# Rocketometer2148_MPU6000.net
KiCad netlist of a schematic drawn in EAGLE
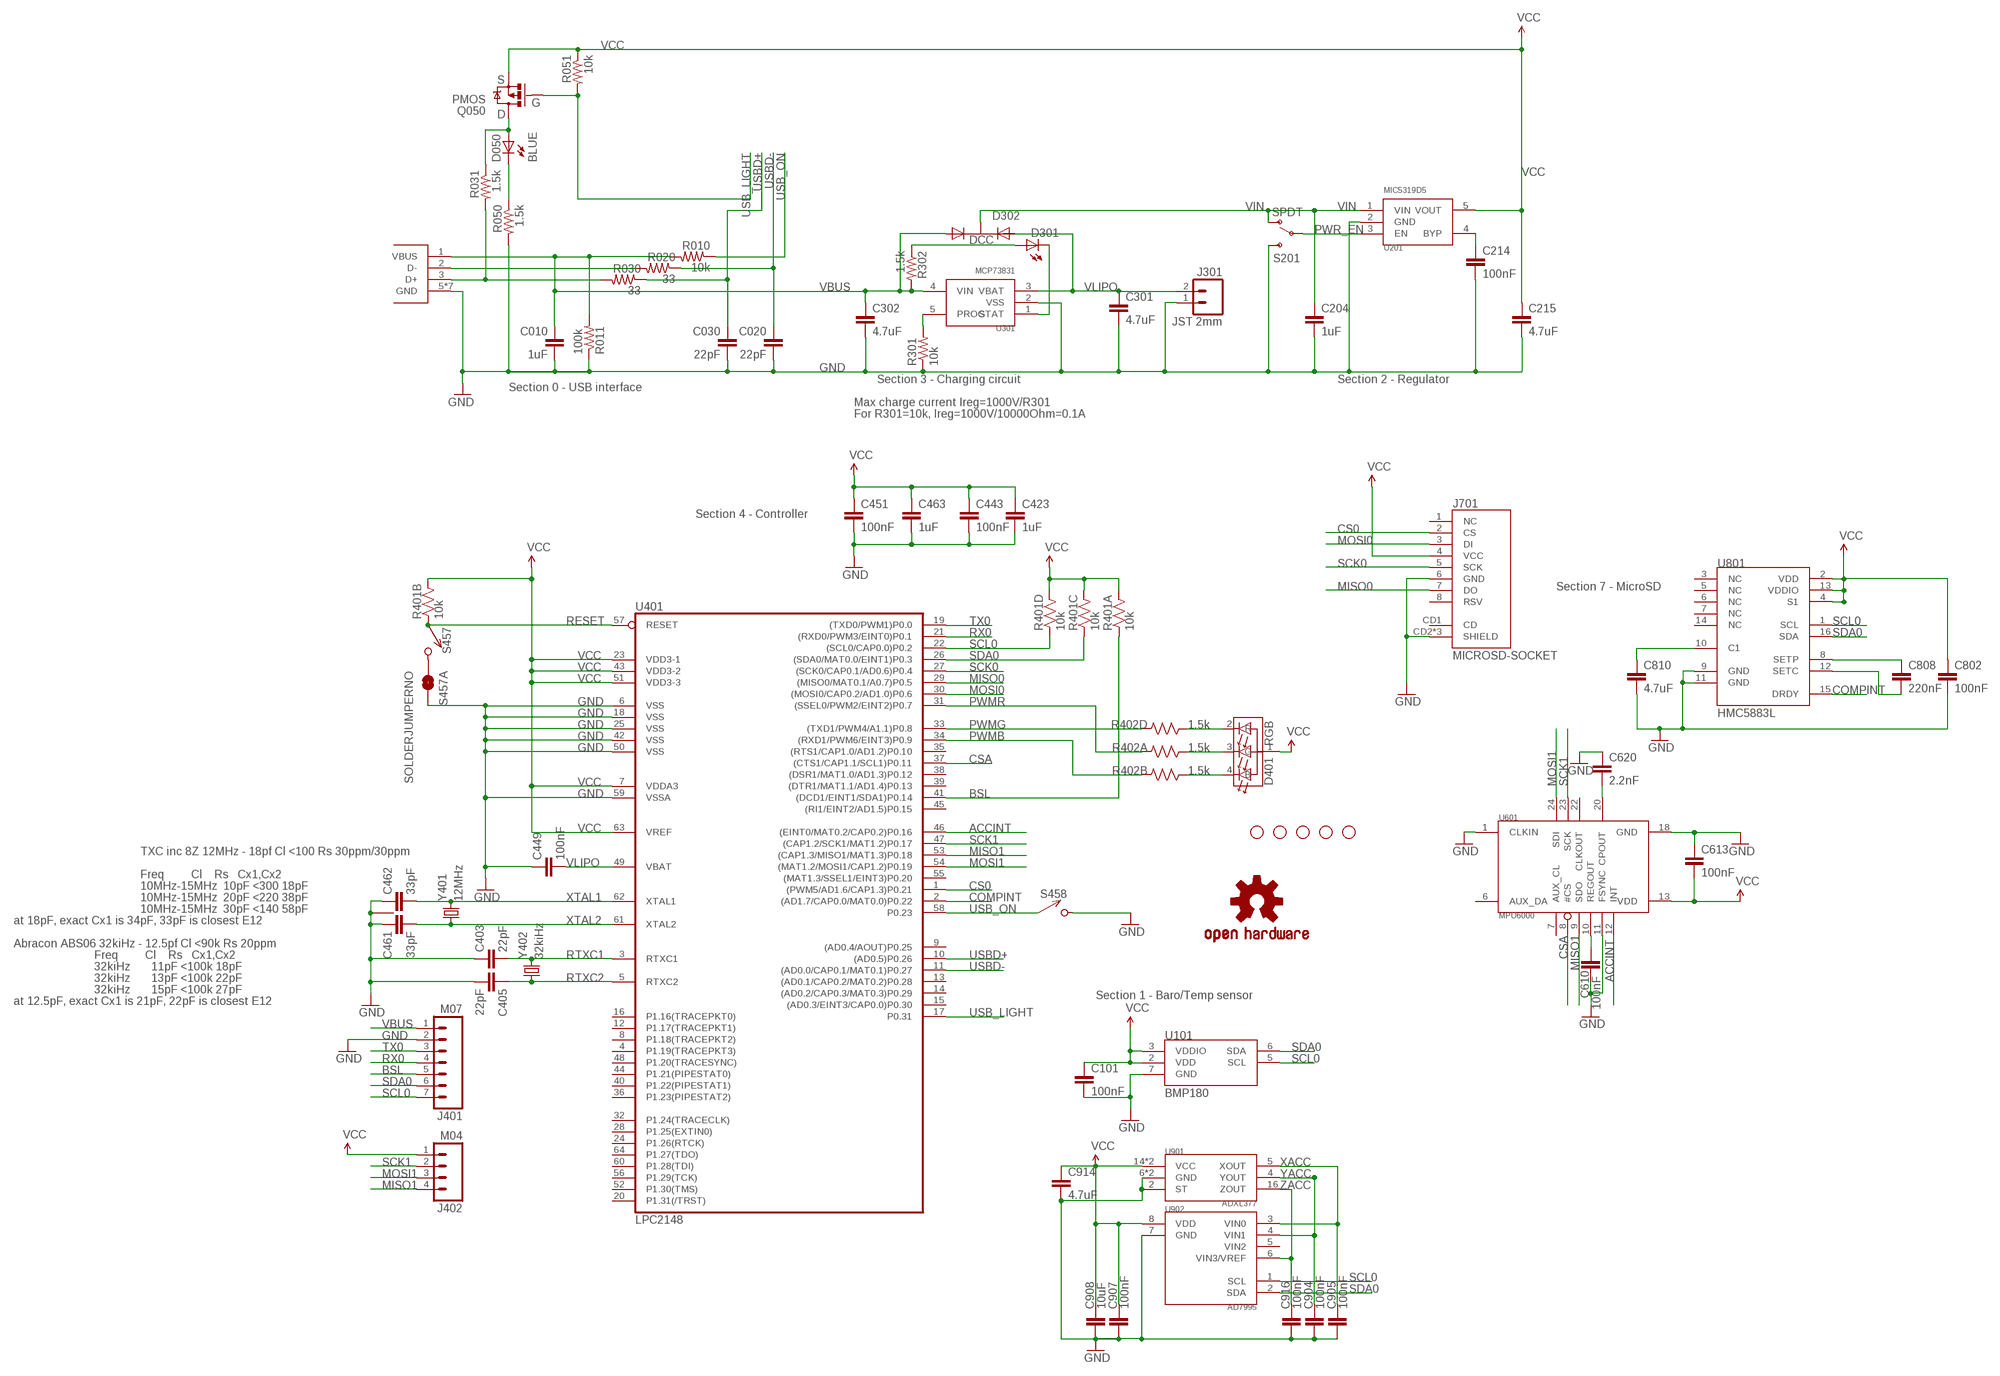
[diagram p0: schematic, sheet 1]

(export (version "E")
  (design (tool "Eeschema 10.0.6"))
  (components
    (comp (ref "C010")
      (value "1uF")
      (footprint "eagle-import:0402-CAP")
      (libsource (lib "eagle-import") (part "CAP0402-CAP"))
    )
    (comp (ref "C020")
      (value "22pF")
      (footprint "eagle-import:0402-CAP")
      (libsource (lib "eagle-import") (part "CAP0402-CAP"))
    )
    (comp (ref "C030")
      (value "22pF")
      (footprint "eagle-import:0402-CAP")
      (libsource (lib "eagle-import") (part "CAP0402-CAP"))
    )
    (comp (ref "C101")
      (value "100nF")
      (footprint "eagle-import:0402-CAP")
      (libsource (lib "eagle-import") (part "CAP0402-CAP"))
    )
    (comp (ref "C204")
      (value "1uF")
      (footprint "eagle-import:0402-CAP")
      (libsource (lib "eagle-import") (part "CAP0402-CAP"))
    )
    (comp (ref "C214")
      (value "100nF")
      (footprint "eagle-import:0402-CAP")
      (libsource (lib "eagle-import") (part "CAP0402-CAP"))
    )
    (comp (ref "C215")
      (value "4.7uF")
      (footprint "eagle-import:0402-CAP")
      (libsource (lib "eagle-import") (part "CAP0402-CAP"))
    )
    (comp (ref "C301")
      (value "4.7uF")
      (footprint "eagle-import:0402-CAP")
      (libsource (lib "eagle-import") (part "CAP0402-CAP"))
    )
    (comp (ref "C302")
      (value "4.7uF")
      (footprint "eagle-import:0402-CAP")
      (libsource (lib "eagle-import") (part "CAP0402-CAP"))
    )
    (comp (ref "C403")
      (value "22pF")
      (footprint "eagle-import:0402-CAP")
      (libsource (lib "eagle-import") (part "CAP0402-CAP"))
    )
    (comp (ref "C405")
      (value "22pF")
      (footprint "eagle-import:0402-CAP")
      (libsource (lib "eagle-import") (part "CAP0402-CAP"))
    )
    (comp (ref "C423")
      (value "1uF")
      (footprint "eagle-import:0402-CAP")
      (libsource (lib "eagle-import") (part "CAP0402-CAP"))
    )
    (comp (ref "C443")
      (value "100nF")
      (footprint "eagle-import:0402-CAP")
      (libsource (lib "eagle-import") (part "CAP0402-CAP"))
    )
    (comp (ref "C449")
      (value "100nF")
      (footprint "eagle-import:0402-CAP")
      (libsource (lib "eagle-import") (part "CAP0402-CAP"))
    )
    (comp (ref "C451")
      (value "100nF")
      (footprint "eagle-import:0402-CAP")
      (libsource (lib "eagle-import") (part "CAP0402-CAP"))
    )
    (comp (ref "C461")
      (value "33pF")
      (footprint "eagle-import:0402-CAP")
      (libsource (lib "eagle-import") (part "CAP0402-CAP"))
    )
    (comp (ref "C462")
      (value "33pF")
      (footprint "eagle-import:0402-CAP")
      (libsource (lib "eagle-import") (part "CAP0402-CAP"))
    )
    (comp (ref "C463")
      (value "1uF")
      (footprint "eagle-import:0402-CAP")
      (libsource (lib "eagle-import") (part "CAP0402-CAP"))
    )
    (comp (ref "C610")
      (value "100nF")
      (footprint "eagle-import:0402-CAP")
      (libsource (lib "eagle-import") (part "CAP0402-CAP"))
    )
    (comp (ref "C613")
      (value "100nF")
      (footprint "eagle-import:0402-CAP")
      (libsource (lib "eagle-import") (part "CAP0402-CAP"))
    )
    (comp (ref "C620")
      (value "2.2nF")
      (footprint "eagle-import:0402-CAP")
      (libsource (lib "eagle-import") (part "CAP0402-CAP"))
    )
    (comp (ref "C802")
      (value "100nF")
      (footprint "eagle-import:0402-CAP")
      (libsource (lib "eagle-import") (part "CAP0402-CAP"))
    )
    (comp (ref "C808")
      (value "220nF")
      (footprint "eagle-import:0402-CAP")
      (libsource (lib "eagle-import") (part "CAP0402-CAP"))
    )
    (comp (ref "C810")
      (value "4.7uF")
      (footprint "eagle-import:0402-CAP")
      (libsource (lib "eagle-import") (part "CAP0402-CAP"))
    )
    (comp (ref "C904")
      (value "100nF")
      (footprint "eagle-import:0402-CAP")
      (libsource (lib "eagle-import") (part "CAP0402-CAP"))
    )
    (comp (ref "C905")
      (value "100nF")
      (footprint "eagle-import:0402-CAP")
      (libsource (lib "eagle-import") (part "CAP0402-CAP"))
    )
    (comp (ref "C907")
      (value "100nF")
      (footprint "eagle-import:0402-CAP")
      (libsource (lib "eagle-import") (part "SparkFun-Passives_CAP0402-CAP"))
    )
    (comp (ref "C908")
      (value "10uF")
      (footprint "eagle-import:0603-CAP")
      (libsource (lib "eagle-import") (part "CAP0603-CAP"))
    )
    (comp (ref "C914")
      (value "4.7uF")
      (footprint "eagle-import:0402-CAP")
      (libsource (lib "eagle-import") (part "CAP0402-CAP"))
    )
    (comp (ref "C916")
      (value "100nF")
      (footprint "eagle-import:0402-CAP")
      (libsource (lib "eagle-import") (part "CAP0402-CAP"))
    )
    (comp (ref "D050")
      (value "BLUE")
      (footprint "eagle-import:LED-0603")
      (libsource (lib "eagle-import") (part "LED0603"))
    )
    (comp (ref "D301")
      (value "YELLOW")
      (footprint "eagle-import:LED-0603")
      (libsource (lib "eagle-import") (part "LED0603"))
    )
    (comp (ref "D302")
      (value "DCC")
      (footprint "eagle-import:SOT-23-3")
      (libsource (lib "eagle-import") (part "PMEG2005CT"))
    )
    (comp (ref "D401")
      (value "RGB")
      (footprint "eagle-import:HSMF-C118")
      (libsource (lib "eagle-import") (part "HSMF-C118"))
    )
    (comp (ref "J001")
      (value "USB_MICROB_JST")
      (footprint "eagle-import:UB-MC5BR3-SD204-4S")
      (libsource (lib "eagle-import") (part "USB_MICROB_JST"))
    )
    (comp (ref "J301")
      (value "JST 2mm")
      (footprint "eagle-import:JST-2-SMD")
      (libsource (lib "eagle-import") (part "M02-JST-2MM-SMT"))
    )
    (comp (ref "J401")
      (value "M07")
      (footprint "eagle-import:1X07")
      (libsource (lib "eagle-import") (part "M07"))
    )
    (comp (ref "J402")
      (value "M04")
      (footprint "eagle-import:1X04")
      (libsource (lib "eagle-import") (part "M04PTH"))
    )
    (comp (ref "J701")
      (value "MICROSD-SOCKET")
      (footprint "eagle-import:MICROSD-SOCKET-PP")
      (libsource (lib "eagle-import") (part "MICROSD-SOCKET"))
    )
    (comp (ref "JP1")
      (value "STAND-OFFTIGHT")
      (footprint "eagle-import:STAND-OFF-TIGHT")
      (libsource (lib "eagle-import") (part "STAND-OFFTIGHT"))
    )
    (comp (ref "JP2")
      (value "STAND-OFFTIGHT")
      (footprint "eagle-import:STAND-OFF-TIGHT")
      (libsource (lib "eagle-import") (part "STAND-OFFTIGHT"))
    )
    (comp (ref "JP3")
      (value "STAND-OFFTIGHT")
      (footprint "eagle-import:STAND-OFF-TIGHT")
      (libsource (lib "eagle-import") (part "STAND-OFFTIGHT"))
    )
    (comp (ref "JP4")
      (value "STAND-OFFTIGHT")
      (footprint "eagle-import:STAND-OFF-TIGHT")
      (libsource (lib "eagle-import") (part "STAND-OFFTIGHT"))
    )
    (comp (ref "JP5")
      (value "STAND-OFFTIGHT")
      (footprint "eagle-import:STAND-OFF-TIGHT")
      (libsource (lib "eagle-import") (part "STAND-OFFTIGHT"))
    )
    (comp (ref "Q050")
      (value "PMOS")
      (footprint "eagle-import:SOT23-3")
      (libsource (lib "eagle-import") (part "MOSFET-PCHANNELSMD"))
    )
    (comp (ref "R010")
      (value "10k")
      (footprint "eagle-import:0402-RES")
      (libsource (lib "eagle-import") (part "RESISTOR0402-RES"))
    )
    (comp (ref "R011")
      (value "100k")
      (footprint "eagle-import:0402-RES")
      (libsource (lib "eagle-import") (part "RESISTOR0402-RES"))
    )
    (comp (ref "R020")
      (value "33")
      (footprint "eagle-import:0402-RES")
      (libsource (lib "eagle-import") (part "RESISTOR0402-RES"))
    )
    (comp (ref "R030")
      (value "33")
      (footprint "eagle-import:0402-RES")
      (libsource (lib "eagle-import") (part "RESISTOR0402-RES"))
    )
    (comp (ref "R031")
      (value "1.5k")
      (footprint "eagle-import:0402-RES")
      (libsource (lib "eagle-import") (part "RESISTOR0402-RES"))
    )
    (comp (ref "R050")
      (value "1.5k")
      (footprint "eagle-import:0402-RES")
      (libsource (lib "eagle-import") (part "RESISTOR0402-RES"))
    )
    (comp (ref "R051")
      (value "10k")
      (footprint "eagle-import:0402-RES")
      (libsource (lib "eagle-import") (part "RESISTOR0402-RES"))
    )
    (comp (ref "R301")
      (value "10k")
      (footprint "eagle-import:0402-RES")
      (libsource (lib "eagle-import") (part "RESISTOR0402-RES"))
    )
    (comp (ref "R302")
      (value "1.5k")
      (footprint "eagle-import:0402-RES")
      (libsource (lib "eagle-import") (part "RESISTOR0402-RES"))
    )
    (comp (ref "R401")
      (value "10k")
      (footprint "eagle-import:CRA04")
      (fields (field (name "DIGIKEY") "CRA4S810KCT-ND"))
      (libsource (lib "eagle-import") (part "RP404"))
    )
    (comp (ref "R402")
      (value "1.5k")
      (footprint "eagle-import:CRA04")
      (fields (field (name "DIGIKEY") "CRA4S81.5KCT-ND"))
      (libsource (lib "eagle-import") (part "RP404"))
    )
    (comp (ref "S201")
      (value "SPDT")
      (footprint "eagle-import:AYZ0202")
      (libsource (lib "eagle-import") (part "SWITCH-SPSTSMD"))
    )
    (comp (ref "S457")
      (value "B3U-1000P")
      (footprint "eagle-import:B3U-1000P")
      (libsource (lib "eagle-import") (part "B3U-1000P"))
    )
    (comp (ref "S457A")
      (value "SOLDERJUMPERNO")
      (footprint "eagle-import:SJ_2S-NO")
      (libsource (lib "eagle-import") (part "SOLDERJUMPERNO"))
    )
    (comp (ref "S458")
      (value "B3U-1000P")
      (footprint "eagle-import:B3U-1000P")
      (libsource (lib "eagle-import") (part "B3U-1000P"))
    )
    (comp (ref "U$2")
      (value "OSHW-LOGOS")
      (footprint "eagle-import:OSHW-LOGO-S")
      (libsource (lib "eagle-import") (part "OSHW-LOGOS"))
    )
    (comp (ref "U101")
      (value "BMP180")
      (footprint "eagle-import:BMP180")
      (libsource (lib "eagle-import") (part "BMP180"))
    )
    (comp (ref "U201")
      (value "MIC5319D5")
      (footprint "eagle-import:SOT-23-5")
      (libsource (lib "eagle-import") (part "MIC5319D5"))
    )
    (comp (ref "U301")
      (value "MCP73831")
      (footprint "eagle-import:SOT-23-5")
      (libsource (lib "eagle-import") (part "MCP73831"))
    )
    (comp (ref "U401")
      (value "LPC2148")
      (footprint "eagle-import:SQFP-S-10X10-64")
      (libsource (lib "eagle-import") (part "LPC213X"))
    )
    (comp (ref "U601")
      (value "MPU6000")
      (footprint "eagle-import:MPU60X0")
      (libsource (lib "eagle-import") (part "MPU6000"))
    )
    (comp (ref "U801")
      (value "HMC5883L")
      (footprint "eagle-import:16LPCC")
      (libsource (lib "eagle-import") (part "HMC5883LSMD"))
    )
    (comp (ref "U901")
      (value "ADXL377")
      (footprint "eagle-import:ADXL377")
      (libsource (lib "eagle-import") (part "ADXL377"))
    )
    (comp (ref "U902")
      (value "AD7995")
      (footprint "eagle-import:SOT-23-8")
      (libsource (lib "eagle-import") (part "AD799X"))
    )
    (comp (ref "Y401")
      (value "12MHz")
      (footprint "eagle-import:CRYSTAL_SMD_2MM_2_5MM")
      (fields (field (name "DIGIKEY") "887-1487-1-ND"))
      (libsource (lib "eagle-import") (part "CX2520"))
    )
    (comp (ref "Y402")
      (value "32kiHz")
      (footprint "eagle-import:ABS06")
      (libsource (lib "eagle-import") (part "ABS06"))
    )
  )
  (nets
    (net (code "1") (name "/ACCINT") (class "Default")
      (node (ref "U401") (pin "46") (pinfunction "(EINT0/MAT0.2/CAP0.2)P0.16_46") (pintype "bidirectional"))
      (node (ref "U601") (pin "12") (pinfunction "INT_12") (pintype "output"))
    )
    (net (code "2") (name "/BSL") (class "Default")
      (node (ref "J401") (pin "5") (pinfunction "5_5") (pintype "passive"))
      (node (ref "R401") (pin "1") (pinfunction "1_1") (pintype "passive"))
      (node (ref "U401") (pin "41") (pinfunction "(DCD1/EINT1/SDA1)P0.14_41") (pintype "bidirectional"))
    )
    (net (code "3") (name "/COMPINT") (class "Default")
      (node (ref "U401") (pin "2") (pinfunction "(AD1.7/CAP0.0/MAT0.0)P0.22_2") (pintype "bidirectional"))
      (node (ref "U801") (pin "15") (pinfunction "DRDY_15") (pintype "bidirectional"))
    )
    (net (code "4") (name "/CS0") (class "Default")
      (node (ref "J701") (pin "2") (pinfunction "CS_2") (pintype "bidirectional"))
      (node (ref "U401") (pin "1") (pinfunction "(PWM5/AD1.6/CAP1.3)P0.21_1") (pintype "bidirectional"))
    )
    (net (code "5") (name "/CSA") (class "Default")
      (node (ref "U401") (pin "37") (pinfunction "(CTS1/CAP1.1/SCL1)P0.11_37") (pintype "bidirectional"))
      (node (ref "U601") (pin "8") (pinfunction "#CS_8") (pintype "bidirectional"))
    )
    (net (code "6") (name "/MISO0") (class "Default")
      (node (ref "J701") (pin "7") (pinfunction "DO_7") (pintype "bidirectional"))
      (node (ref "U401") (pin "29") (pinfunction "(MISO0/MAT0.1/A0.7)P0.5_29") (pintype "bidirectional"))
    )
    (net (code "7") (name "/MISO1") (class "Default")
      (node (ref "J402") (pin "4") (pinfunction "4_4") (pintype "passive"))
      (node (ref "U401") (pin "53") (pinfunction "(CAP1.3/MISO1/MAT1.3)P0.18_53") (pintype "bidirectional"))
      (node (ref "U601") (pin "9") (pinfunction "SDO_9") (pintype "output"))
    )
    (net (code "8") (name "/MOSI0") (class "Default")
      (node (ref "J701") (pin "3") (pinfunction "DI_3") (pintype "bidirectional"))
      (node (ref "U401") (pin "30") (pinfunction "(MOSI0/CAP0.2/AD1.0)P0.6_30") (pintype "bidirectional"))
    )
    (net (code "9") (name "/MOSI1") (class "Default")
      (node (ref "J402") (pin "3") (pinfunction "3_3") (pintype "passive"))
      (node (ref "U401") (pin "54") (pinfunction "(MAT1.2/MOSI1/CAP1.2)P0.19_54") (pintype "bidirectional"))
      (node (ref "U601") (pin "24") (pinfunction "SDI_24") (pintype "bidirectional"))
    )
    (net (code "10") (name "/PWMB") (class "Default")
      (node (ref "R402") (pin "7") (pinfunction "2_7") (pintype "passive"))
      (node (ref "U401") (pin "34") (pinfunction "(RXD1/PWM6/EINT3)P0.9_34") (pintype "bidirectional"))
    )
    (net (code "11") (name "/PWMG") (class "Default")
      (node (ref "R402") (pin "5") (pinfunction "2_5") (pintype "passive"))
      (node (ref "U401") (pin "33") (pinfunction "(TXD1/PWM4/A1.1)P0.8_33") (pintype "bidirectional"))
    )
    (net (code "12") (name "/PWMR") (class "Default")
      (node (ref "R402") (pin "8") (pinfunction "2_8") (pintype "passive"))
      (node (ref "U401") (pin "31") (pinfunction "(SSEL0/PWM2/EINT2)P0.7_31") (pintype "bidirectional"))
    )
    (net (code "13") (name "/PWR_EN") (class "Default")
      (node (ref "S201") (pin "2") (pinfunction "P_2") (pintype "passive"))
      (node (ref "U201") (pin "3") (pinfunction "EN_3") (pintype "bidirectional"))
    )
    (net (code "14") (name "/RESET") (class "Default")
      (node (ref "R401") (pin "2") (pinfunction "1_2") (pintype "passive"))
      (node (ref "S457") (pin "P$1") (pinfunction "1_P$1") (pintype "bidirectional"))
      (node (ref "U401") (pin "57") (pinfunction "RESET_57") (pintype "input"))
    )
    (net (code "15") (name "/RTXC1") (class "Default")
      (node (ref "C403") (pin "2") (pinfunction "2_2") (pintype "passive"))
      (node (ref "U401") (pin "3") (pinfunction "RTXC1_3") (pintype "input"))
      (node (ref "Y402") (pin "2") (pinfunction "2_2") (pintype "passive"))
    )
    (net (code "16") (name "/RTXC2") (class "Default")
      (node (ref "C405") (pin "1") (pinfunction "1_1") (pintype "passive"))
      (node (ref "U401") (pin "5") (pinfunction "RTXC2_5") (pintype "output"))
      (node (ref "Y402") (pin "1") (pinfunction "1_1") (pintype "passive"))
    )
    (net (code "17") (name "/RX0") (class "Default")
      (node (ref "J401") (pin "4") (pinfunction "4_4") (pintype "passive"))
      (node (ref "U401") (pin "21") (pinfunction "(RXD0/PWM3/EINT0)P0.1_21") (pintype "bidirectional"))
    )
    (net (code "18") (name "/SCK0") (class "Default")
      (node (ref "J701") (pin "5") (pinfunction "SCK_5") (pintype "bidirectional"))
      (node (ref "U401") (pin "27") (pinfunction "(SCK0/CAP0.1/AD0.6)P0.4_27") (pintype "bidirectional"))
    )
    (net (code "19") (name "/SCK1") (class "Default")
      (node (ref "J402") (pin "2") (pinfunction "2_2") (pintype "passive"))
      (node (ref "U401") (pin "47") (pinfunction "(CAP1.2/SCK1/MAT1.2)P0.17_47") (pintype "bidirectional"))
      (node (ref "U601") (pin "23") (pinfunction "SCK_23") (pintype "bidirectional"))
    )
    (net (code "20") (name "/SCL0") (class "Default")
      (node (ref "J401") (pin "7") (pinfunction "7_7") (pintype "passive"))
      (node (ref "R401") (pin "4") (pinfunction "1_4") (pintype "passive"))
      (node (ref "U101") (pin "5") (pinfunction "SCL_5") (pintype "input"))
      (node (ref "U401") (pin "22") (pinfunction "(SCL0/CAP0.0)P0.2_22") (pintype "bidirectional"))
      (node (ref "U801") (pin "1") (pinfunction "SCL_1") (pintype "bidirectional"))
      (node (ref "U902") (pin "1") (pinfunction "SCL_1") (pintype "bidirectional"))
    )
    (net (code "21") (name "/SDA0") (class "Default")
      (node (ref "J401") (pin "6") (pinfunction "6_6") (pintype "passive"))
      (node (ref "R401") (pin "3") (pinfunction "1_3") (pintype "passive"))
      (node (ref "U101") (pin "6") (pinfunction "SDA_6") (pintype "bidirectional"))
      (node (ref "U401") (pin "26") (pinfunction "(SDA0/MAT0.0/EINT1)P0.3_26") (pintype "bidirectional"))
      (node (ref "U801") (pin "16") (pinfunction "SDA_16") (pintype "bidirectional"))
      (node (ref "U902") (pin "2") (pinfunction "SDA_2") (pintype "bidirectional"))
    )
    (net (code "22") (name "/TX0") (class "Default")
      (node (ref "J401") (pin "3") (pinfunction "3_3") (pintype "passive"))
      (node (ref "U401") (pin "19") (pinfunction "(TXD0/PWM1)P0.0_19") (pintype "bidirectional"))
    )
    (net (code "23") (name "/USBD+") (class "Default")
      (node (ref "C030") (pin "1") (pinfunction "1_1") (pintype "passive"))
      (node (ref "R030") (pin "1") (pinfunction "1_1") (pintype "passive"))
      (node (ref "U401") (pin "10") (pinfunction "(AD0.5)P0.26_10") (pintype "bidirectional"))
    )
    (net (code "24") (name "/USBD-") (class "Default")
      (node (ref "C020") (pin "1") (pinfunction "1_1") (pintype "passive"))
      (node (ref "R020") (pin "1") (pinfunction "1_1") (pintype "passive"))
      (node (ref "U401") (pin "11") (pinfunction "(AD0.0/CAP0.1/MAT0.1)P0.27_11") (pintype "bidirectional"))
    )
    (net (code "25") (name "/USB_LIGHT") (class "Default")
      (node (ref "Q050") (pin "1") (pinfunction "G_1") (pintype "passive"))
      (node (ref "R051") (pin "2") (pinfunction "2_2") (pintype "passive"))
      (node (ref "U401") (pin "17") (pinfunction "P0.31_17") (pintype "output"))
    )
    (net (code "26") (name "/USB_ON") (class "Default")
      (node (ref "R010") (pin "1") (pinfunction "1_1") (pintype "passive"))
      (node (ref "S458") (pin "P$1") (pinfunction "1_P$1") (pintype "bidirectional"))
      (node (ref "U401") (pin "58") (pinfunction "P0.23_58") (pintype "bidirectional"))
    )
    (net (code "27") (name "/VBUS") (class "Default")
      (node (ref "C010") (pin "1") (pinfunction "1_1") (pintype "passive"))
      (node (ref "C302") (pin "1") (pinfunction "1_1") (pintype "passive"))
      (node (ref "D302") (pin "1") (pinfunction "A1_1") (pintype "passive"))
      (node (ref "J001") (pin "1") (pinfunction "VBUS_1") (pintype "bidirectional"))
      (node (ref "J401") (pin "1") (pinfunction "1_1") (pintype "passive"))
      (node (ref "R010") (pin "2") (pinfunction "2_2") (pintype "passive"))
      (node (ref "R011") (pin "2") (pinfunction "2_2") (pintype "passive"))
      (node (ref "R302") (pin "2") (pinfunction "2_2") (pintype "passive"))
      (node (ref "U301") (pin "4") (pinfunction "VIN_4") (pintype "bidirectional"))
    )
    (net (code "28") (name "/VIN") (class "Default")
      (node (ref "C204") (pin "1") (pinfunction "1_1") (pintype "passive"))
      (node (ref "D302") (pin "3") (pinfunction "K_3") (pintype "passive"))
      (node (ref "S201") (pin "1") (pinfunction "O_1") (pintype "passive"))
      (node (ref "U201") (pin "1") (pinfunction "VIN_1") (pintype "bidirectional"))
    )
    (net (code "29") (name "/VLIPO") (class "Default")
      (node (ref "C301") (pin "1") (pinfunction "1_1") (pintype "passive"))
      (node (ref "C449") (pin "2") (pinfunction "2_2") (pintype "passive"))
      (node (ref "D302") (pin "2") (pinfunction "A2_2") (pintype "passive"))
      (node (ref "J301") (pin "2") (pinfunction "2_2") (pintype "passive"))
      (node (ref "U301") (pin "3") (pinfunction "VBAT_3") (pintype "bidirectional"))
      (node (ref "U401") (pin "49") (pinfunction "VBAT_49") (pintype "power_in"))
    )
    (net (code "30") (name "/XACC") (class "Default")
      (node (ref "C905") (pin "1") (pinfunction "1_1") (pintype "passive"))
      (node (ref "U901") (pin "5") (pinfunction "XOUT_5") (pintype "bidirectional"))
      (node (ref "U902") (pin "3") (pinfunction "VIN0_3") (pintype "bidirectional"))
    )
    (net (code "31") (name "/XTAL1") (class "Default")
      (node (ref "C462") (pin "2") (pinfunction "2_2") (pintype "passive"))
      (node (ref "U401") (pin "62") (pinfunction "XTAL1_62") (pintype "input"))
      (node (ref "Y401") (pin "3") (pinfunction "2_3") (pintype "passive"))
    )
    (net (code "32") (name "/XTAL2") (class "Default")
      (node (ref "C461") (pin "2") (pinfunction "2_2") (pintype "passive"))
      (node (ref "U401") (pin "61") (pinfunction "XTAL2_61") (pintype "output"))
      (node (ref "Y401") (pin "1") (pinfunction "1_1") (pintype "passive"))
    )
    (net (code "33") (name "/YACC") (class "Default")
      (node (ref "C904") (pin "1") (pinfunction "1_1") (pintype "passive"))
      (node (ref "U901") (pin "4") (pinfunction "YOUT_4") (pintype "bidirectional"))
      (node (ref "U902") (pin "4") (pinfunction "VIN1_4") (pintype "bidirectional"))
    )
    (net (code "34") (name "/ZACC") (class "Default")
      (node (ref "C916") (pin "1") (pinfunction "1_1") (pintype "passive"))
      (node (ref "U901") (pin "16") (pinfunction "ZOUT_16") (pintype "bidirectional"))
      (node (ref "U902") (pin "6") (pinfunction "VIN3/VREF_6") (pintype "bidirectional"))
    )
    (net (code "35") (name "GND") (class "Default")
      (node (ref "C010") (pin "2") (pinfunction "2_2") (pintype "passive"))
      (node (ref "C020") (pin "2") (pinfunction "2_2") (pintype "passive"))
      (node (ref "C030") (pin "2") (pinfunction "2_2") (pintype "passive"))
      (node (ref "C101") (pin "2") (pinfunction "2_2") (pintype "passive"))
      (node (ref "C204") (pin "2") (pinfunction "2_2") (pintype "passive"))
      (node (ref "C214") (pin "2") (pinfunction "2_2") (pintype "passive"))
      (node (ref "C215") (pin "2") (pinfunction "2_2") (pintype "passive"))
      (node (ref "C301") (pin "2") (pinfunction "2_2") (pintype "passive"))
      (node (ref "C302") (pin "2") (pinfunction "2_2") (pintype "passive"))
      (node (ref "C403") (pin "1") (pinfunction "1_1") (pintype "passive"))
      (node (ref "C405") (pin "2") (pinfunction "2_2") (pintype "passive"))
      (node (ref "C423") (pin "2") (pinfunction "2_2") (pintype "passive"))
      (node (ref "C443") (pin "2") (pinfunction "2_2") (pintype "passive"))
      (node (ref "C449") (pin "1") (pinfunction "1_1") (pintype "passive"))
      (node (ref "C451") (pin "2") (pinfunction "2_2") (pintype "passive"))
      (node (ref "C461") (pin "1") (pinfunction "1_1") (pintype "passive"))
      (node (ref "C462") (pin "1") (pinfunction "1_1") (pintype "passive"))
      (node (ref "C463") (pin "2") (pinfunction "2_2") (pintype "passive"))
      (node (ref "C610") (pin "2") (pinfunction "2_2") (pintype "passive"))
      (node (ref "C613") (pin "1") (pinfunction "1_1") (pintype "passive"))
      (node (ref "C620") (pin "1") (pinfunction "1_1") (pintype "passive"))
      (node (ref "C802") (pin "2") (pinfunction "2_2") (pintype "passive"))
      (node (ref "C810") (pin "2") (pinfunction "2_2") (pintype "passive"))
      (node (ref "C904") (pin "2") (pinfunction "2_2") (pintype "passive"))
      (node (ref "C905") (pin "2") (pinfunction "2_2") (pintype "passive"))
      (node (ref "C907") (pin "2") (pinfunction "2_2") (pintype "passive"))
      (node (ref "C908") (pin "2") (pinfunction "2_2") (pintype "passive"))
      (node (ref "C914") (pin "2") (pinfunction "2_2") (pintype "passive"))
      (node (ref "C916") (pin "2") (pinfunction "2_2") (pintype "passive"))
      (node (ref "J001") (pin "5") (pinfunction "GND_5") (pintype "bidirectional"))
      (node (ref "J001") (pin "P$10") (pinfunction "GND_P$10") (pintype "bidirectional"))
      (node (ref "J001") (pin "P$11") (pinfunction "GND_P$11") (pintype "bidirectional"))
      (node (ref "J001") (pin "P$6") (pinfunction "GND_P$6") (pintype "bidirectional"))
      (node (ref "J001") (pin "P$7") (pinfunction "GND_P$7") (pintype "bidirectional"))
      (node (ref "J001") (pin "P$8") (pinfunction "GND_P$8") (pintype "bidirectional"))
      (node (ref "J001") (pin "P$9") (pinfunction "GND_P$9") (pintype "bidirectional"))
      (node (ref "J301") (pin "1") (pinfunction "1_1") (pintype "passive"))
      (node (ref "J401") (pin "2") (pinfunction "2_2") (pintype "passive"))
      (node (ref "J701") (pin "6") (pinfunction "GND_6") (pintype "bidirectional"))
      (node (ref "J701") (pin "CD2") (pinfunction "SHIELD_CD2") (pintype "bidirectional"))
      (node (ref "J701") (pin "GND1") (pinfunction "SHIELD_GND1") (pintype "bidirectional"))
      (node (ref "J701") (pin "GND3") (pinfunction "SHIELD_GND3") (pintype "bidirectional"))
      (node (ref "R011") (pin "1") (pinfunction "1_1") (pintype "passive"))
      (node (ref "R050") (pin "2") (pinfunction "2_2") (pintype "passive"))
      (node (ref "R301") (pin "1") (pinfunction "1_1") (pintype "passive"))
      (node (ref "S201") (pin "3") (pinfunction "S_3") (pintype "passive"))
      (node (ref "S457A") (pin "2") (pinfunction "2_2") (pintype "passive"))
      (node (ref "S458") (pin "P$2") (pinfunction "2_P$2") (pintype "bidirectional"))
      (node (ref "U101") (pin "7") (pinfunction "GND_7") (pintype "power_in"))
      (node (ref "U201") (pin "2") (pinfunction "GND_2") (pintype "bidirectional"))
      (node (ref "U301") (pin "2") (pinfunction "VSS_2") (pintype "bidirectional"))
      (node (ref "U401") (pin "18") (pinfunction "VSS_18") (pintype "power_in"))
      (node (ref "U401") (pin "25") (pinfunction "VSS_25") (pintype "power_in"))
      (node (ref "U401") (pin "42") (pinfunction "VSS_42") (pintype "power_in"))
      (node (ref "U401") (pin "50") (pinfunction "VSS_50") (pintype "power_in"))
      (node (ref "U401") (pin "59") (pinfunction "VSSA_59") (pintype "power_in"))
      (node (ref "U401") (pin "6") (pinfunction "VSS_6") (pintype "power_in"))
      (node (ref "U601") (pin "1") (pinfunction "CLKIN_1") (pintype "input"))
      (node (ref "U601") (pin "11") (pinfunction "FSYNC_11") (pintype "bidirectional"))
      (node (ref "U601") (pin "18") (pinfunction "GND_18") (pintype "power_in"))
      (node (ref "U801") (pin "11") (pinfunction "GND_11") (pintype "bidirectional"))
      (node (ref "U801") (pin "9") (pinfunction "GND_9") (pintype "bidirectional"))
      (node (ref "U901") (pin "2") (pinfunction "ST_2") (pintype "bidirectional"))
      (node (ref "U901") (pin "6") (pinfunction "GND_6") (pintype "bidirectional"))
      (node (ref "U901") (pin "7") (pinfunction "GND_7") (pintype "bidirectional"))
      (node (ref "U902") (pin "7") (pinfunction "GND_7") (pintype "bidirectional"))
      (node (ref "Y401") (pin "2") (pinfunction "1_2") (pintype "bidirectional"))
      (node (ref "Y401") (pin "4") (pinfunction "1_4") (pintype "bidirectional"))
    )
    (net (code "36") (name "Net-(D050-PadC)") (class "Default")
      (node (ref "D050") (pin "C") (pinfunction "C_C") (pintype "passive"))
      (node (ref "R050") (pin "1") (pinfunction "1_1") (pintype "passive"))
    )
    (net (code "37") (name "Net-(D301-PadA)") (class "Default")
      (node (ref "D301") (pin "A") (pinfunction "A_A") (pintype "passive"))
      (node (ref "R302") (pin "1") (pinfunction "1_1") (pintype "passive"))
    )
    (net (code "38") (name "Net-(D401-B)") (class "Default")
      (node (ref "D401") (pin "4") (pinfunction "B_4") (pintype "passive"))
      (node (ref "R402") (pin "2") (pinfunction "1_2") (pintype "passive"))
    )
    (net (code "39") (name "Net-(D401-G)") (class "Default")
      (node (ref "D401") (pin "3") (pinfunction "G_3") (pintype "passive"))
      (node (ref "R402") (pin "1") (pinfunction "1_1") (pintype "passive"))
    )
    (net (code "40") (name "Net-(D401-R)") (class "Default")
      (node (ref "D401") (pin "2") (pinfunction "R_2") (pintype "passive"))
      (node (ref "R402") (pin "4") (pinfunction "1_4") (pintype "passive"))
    )
    (net (code "41") (name "Net-(J001-D+)") (class "Default")
      (node (ref "J001") (pin "3") (pinfunction "D+_3") (pintype "bidirectional"))
      (node (ref "R030") (pin "2") (pinfunction "2_2") (pintype "passive"))
      (node (ref "R031") (pin "2") (pinfunction "2_2") (pintype "passive"))
    )
    (net (code "42") (name "Net-(J001-D-)") (class "Default")
      (node (ref "J001") (pin "2") (pinfunction "D-_2") (pintype "bidirectional"))
      (node (ref "R020") (pin "2") (pinfunction "2_2") (pintype "passive"))
    )
    (net (code "43") (name "Net-(Q050-D)") (class "Default")
      (node (ref "D050") (pin "A") (pinfunction "A_A") (pintype "passive"))
      (node (ref "Q050") (pin "3") (pinfunction "D_3") (pintype "passive"))
      (node (ref "R031") (pin "1") (pinfunction "1_1") (pintype "passive"))
    )
    (net (code "44") (name "Net-(S457-2)") (class "Default")
      (node (ref "S457") (pin "P$2") (pinfunction "2_P$2") (pintype "bidirectional"))
      (node (ref "S457A") (pin "1") (pinfunction "1_1") (pintype "passive"))
    )
    (net (code "45") (name "Net-(U201-BYP)") (class "Default")
      (node (ref "C214") (pin "1") (pinfunction "1_1") (pintype "passive"))
      (node (ref "U201") (pin "4") (pinfunction "BYP_4") (pintype "bidirectional"))
    )
    (net (code "46") (name "Net-(U301-PROG)") (class "Default")
      (node (ref "R301") (pin "2") (pinfunction "2_2") (pintype "passive"))
      (node (ref "U301") (pin "5") (pinfunction "PROG_5") (pintype "bidirectional"))
    )
    (net (code "47") (name "Net-(U301-STAT)") (class "Default")
      (node (ref "D301") (pin "C") (pinfunction "C_C") (pintype "passive"))
      (node (ref "U301") (pin "1") (pinfunction "STAT_1") (pintype "bidirectional"))
    )
    (net (code "48") (name "Net-(U601-CPOUT)") (class "Default")
      (node (ref "C620") (pin "2") (pinfunction "2_2") (pintype "passive"))
      (node (ref "U601") (pin "20") (pinfunction "CPOUT_20") (pintype "output"))
    )
    (net (code "49") (name "Net-(U601-REGOUT)") (class "Default")
      (node (ref "C610") (pin "1") (pinfunction "1_1") (pintype "passive"))
      (node (ref "U601") (pin "10") (pinfunction "REGOUT_10") (pintype "bidirectional"))
    )
    (net (code "50") (name "Net-(U801-C1)") (class "Default")
      (node (ref "C810") (pin "1") (pinfunction "1_1") (pintype "passive"))
      (node (ref "U801") (pin "10") (pinfunction "C1_10") (pintype "bidirectional"))
    )
    (net (code "51") (name "Net-(U801-SETC)") (class "Default")
      (node (ref "C808") (pin "2") (pinfunction "2_2") (pintype "passive"))
      (node (ref "U801") (pin "12") (pinfunction "SETC_12") (pintype "bidirectional"))
    )
    (net (code "52") (name "Net-(U801-SETP)") (class "Default")
      (node (ref "C808") (pin "1") (pinfunction "1_1") (pintype "passive"))
      (node (ref "U801") (pin "8") (pinfunction "SETP_8") (pintype "bidirectional"))
    )
    (net (code "53") (name "VCC") (class "Default")
      (node (ref "C101") (pin "1") (pinfunction "1_1") (pintype "passive"))
      (node (ref "C215") (pin "1") (pinfunction "1_1") (pintype "passive"))
      (node (ref "C423") (pin "1") (pinfunction "1_1") (pintype "passive"))
      (node (ref "C443") (pin "1") (pinfunction "1_1") (pintype "passive"))
      (node (ref "C451") (pin "1") (pinfunction "1_1") (pintype "passive"))
      (node (ref "C463") (pin "1") (pinfunction "1_1") (pintype "passive"))
      (node (ref "C613") (pin "2") (pinfunction "2_2") (pintype "passive"))
      (node (ref "C802") (pin "1") (pinfunction "1_1") (pintype "passive"))
      (node (ref "C907") (pin "1") (pinfunction "1_1") (pintype "passive"))
      (node (ref "C908") (pin "1") (pinfunction "1_1") (pintype "passive"))
      (node (ref "C914") (pin "1") (pinfunction "1_1") (pintype "passive"))
      (node (ref "D401") (pin "1") (pinfunction "A_1") (pintype "passive"))
      (node (ref "J402") (pin "1") (pinfunction "1_1") (pintype "passive"))
      (node (ref "J701") (pin "4") (pinfunction "VCC_4") (pintype "bidirectional"))
      (node (ref "Q050") (pin "2") (pinfunction "S_2") (pintype "passive"))
      (node (ref "R051") (pin "1") (pinfunction "1_1") (pintype "passive"))
      (node (ref "R401") (pin "5") (pinfunction "2_5") (pintype "passive"))
      (node (ref "R401") (pin "6") (pinfunction "2_6") (pintype "passive"))
      (node (ref "R401") (pin "7") (pinfunction "2_7") (pintype "passive"))
      (node (ref "R401") (pin "8") (pinfunction "2_8") (pintype "passive"))
      (node (ref "U101") (pin "2") (pinfunction "VDD_2") (pintype "power_in"))
      (node (ref "U101") (pin "3") (pinfunction "VDDIO_3") (pintype "power_in"))
      (node (ref "U201") (pin "5") (pinfunction "VOUT_5") (pintype "bidirectional"))
      (node (ref "U401") (pin "23") (pinfunction "VDD3-1_23") (pintype "power_in"))
      (node (ref "U401") (pin "43") (pinfunction "VDD3-2_43") (pintype "power_in"))
      (node (ref "U401") (pin "51") (pinfunction "VDD3-3_51") (pintype "power_in"))
      (node (ref "U401") (pin "63") (pinfunction "VREF_63") (pintype "input"))
      (node (ref "U401") (pin "7") (pinfunction "VDDA3_7") (pintype "power_in"))
      (node (ref "U601") (pin "13") (pinfunction "VDD_13") (pintype "power_in"))
      (node (ref "U801") (pin "13") (pinfunction "VDDIO_13") (pintype "bidirectional"))
      (node (ref "U801") (pin "2") (pinfunction "VDD_2") (pintype "bidirectional"))
      (node (ref "U801") (pin "4") (pinfunction "S1_4") (pintype "bidirectional"))
      (node (ref "U901") (pin "14") (pinfunction "VCC_14") (pintype "bidirectional"))
      (node (ref "U901") (pin "15") (pinfunction "VCC_15") (pintype "bidirectional"))
      (node (ref "U902") (pin "8") (pinfunction "VDD_8") (pintype "bidirectional"))
    )
    (net (code "54") (name "unconnected-(J701-CD-PadCD1)") (class "Default")
      (node (ref "J701") (pin "CD1") (pinfunction "CD_CD1") (pintype "bidirectional"))
    )
    (net (code "55") (name "unconnected-(J701-NC-Pad1)") (class "Default")
      (node (ref "J701") (pin "1") (pinfunction "NC_1") (pintype "bidirectional"))
    )
    (net (code "56") (name "unconnected-(J701-RSV-Pad8)") (class "Default")
      (node (ref "J701") (pin "8") (pinfunction "RSV_8") (pintype "bidirectional"))
    )
    (net (code "57") (name "unconnected-(U401-(AD0.1{slash}CAP0.2{slash}MAT0.2)P0.28-Pad13)") (class "Default")
      (node (ref "U401") (pin "13") (pinfunction "(AD0.1/CAP0.2/MAT0.2)P0.28_13") (pintype "bidirectional"))
    )
    (net (code "58") (name "unconnected-(U401-(AD0.2{slash}CAP0.3{slash}MAT0.3)P0.29-Pad14)") (class "Default")
      (node (ref "U401") (pin "14") (pinfunction "(AD0.2/CAP0.3/MAT0.3)P0.29_14") (pintype "bidirectional"))
    )
    (net (code "59") (name "unconnected-(U401-(AD0.3{slash}EINT3{slash}CAP0.0)P0.30-Pad15)") (class "Default")
      (node (ref "U401") (pin "15") (pinfunction "(AD0.3/EINT3/CAP0.0)P0.30_15") (pintype "bidirectional"))
    )
    (net (code "60") (name "unconnected-(U401-(AD0.4{slash}AOUT)P0.25-Pad9)") (class "Default")
      (node (ref "U401") (pin "9") (pinfunction "(AD0.4/AOUT)P0.25_9") (pintype "bidirectional"))
    )
    (net (code "61") (name "unconnected-(U401-(DSR1{slash}MAT1.0{slash}AD1.3)P0.12-Pad38)") (class "Default")
      (node (ref "U401") (pin "38") (pinfunction "(DSR1/MAT1.0/AD1.3)P0.12_38") (pintype "bidirectional"))
    )
    (net (code "62") (name "unconnected-(U401-(DTR1{slash}MAT1.1{slash}AD1.4)P0.13-Pad39)") (class "Default")
      (node (ref "U401") (pin "39") (pinfunction "(DTR1/MAT1.1/AD1.4)P0.13_39") (pintype "bidirectional"))
    )
    (net (code "63") (name "unconnected-(U401-(MAT1.3{slash}SSEL1{slash}EINT3)P0.20-Pad55)") (class "Default")
      (node (ref "U401") (pin "55") (pinfunction "(MAT1.3/SSEL1/EINT3)P0.20_55") (pintype "bidirectional"))
    )
    (net (code "64") (name "unconnected-(U401-(RI1{slash}EINT2{slash}AD1.5)P0.15-Pad45)") (class "Default")
      (node (ref "U401") (pin "45") (pinfunction "(RI1/EINT2/AD1.5)P0.15_45") (pintype "bidirectional"))
    )
    (net (code "65") (name "unconnected-(U401-(RTS1{slash}CAP1.0{slash}AD1.2)P0.10-Pad35)") (class "Default")
      (node (ref "U401") (pin "35") (pinfunction "(RTS1/CAP1.0/AD1.2)P0.10_35") (pintype "bidirectional"))
    )
    (net (code "66") (name "unconnected-(U401-P1.16(TRACEPKT0)-Pad16)") (class "Default")
      (node (ref "U401") (pin "16") (pinfunction "P1.16(TRACEPKT0)_16") (pintype "bidirectional"))
    )
    (net (code "67") (name "unconnected-(U401-P1.17(TRACEPKT1)-Pad12)") (class "Default")
      (node (ref "U401") (pin "12") (pinfunction "P1.17(TRACEPKT1)_12") (pintype "bidirectional"))
    )
    (net (code "68") (name "unconnected-(U401-P1.18(TRACEPKT2)-Pad8)") (class "Default")
      (node (ref "U401") (pin "8") (pinfunction "P1.18(TRACEPKT2)_8") (pintype "bidirectional"))
    )
    (net (code "69") (name "unconnected-(U401-P1.19(TRACEPKT3)-Pad4)") (class "Default")
      (node (ref "U401") (pin "4") (pinfunction "P1.19(TRACEPKT3)_4") (pintype "bidirectional"))
    )
    (net (code "70") (name "unconnected-(U401-P1.20(TRACESYNC)-Pad48)") (class "Default")
      (node (ref "U401") (pin "48") (pinfunction "P1.20(TRACESYNC)_48") (pintype "bidirectional"))
    )
    (net (code "71") (name "unconnected-(U401-P1.21(PIPESTAT0)-Pad44)") (class "Default")
      (node (ref "U401") (pin "44") (pinfunction "P1.21(PIPESTAT0)_44") (pintype "bidirectional"))
    )
    (net (code "72") (name "unconnected-(U401-P1.22(PIPESTAT1)-Pad40)") (class "Default")
      (node (ref "U401") (pin "40") (pinfunction "P1.22(PIPESTAT1)_40") (pintype "bidirectional"))
    )
    (net (code "73") (name "unconnected-(U401-P1.23(PIPESTAT2)-Pad36)") (class "Default")
      (node (ref "U401") (pin "36") (pinfunction "P1.23(PIPESTAT2)_36") (pintype "bidirectional"))
    )
    (net (code "74") (name "unconnected-(U401-P1.24(TRACECLK)-Pad32)") (class "Default")
      (node (ref "U401") (pin "32") (pinfunction "P1.24(TRACECLK)_32") (pintype "bidirectional"))
    )
    (net (code "75") (name "unconnected-(U401-P1.25(EXTIN0)-Pad28)") (class "Default")
      (node (ref "U401") (pin "28") (pinfunction "P1.25(EXTIN0)_28") (pintype "bidirectional"))
    )
    (net (code "76") (name "unconnected-(U401-P1.26(RTCK)-Pad24)") (class "Default")
      (node (ref "U401") (pin "24") (pinfunction "P1.26(RTCK)_24") (pintype "bidirectional"))
    )
    (net (code "77") (name "unconnected-(U401-P1.27(TDO)-Pad64)") (class "Default")
      (node (ref "U401") (pin "64") (pinfunction "P1.27(TDO)_64") (pintype "bidirectional"))
    )
    (net (code "78") (name "unconnected-(U401-P1.28(TDI)-Pad60)") (class "Default")
      (node (ref "U401") (pin "60") (pinfunction "P1.28(TDI)_60") (pintype "bidirectional"))
    )
    (net (code "79") (name "unconnected-(U401-P1.29(TCK)-Pad56)") (class "Default")
      (node (ref "U401") (pin "56") (pinfunction "P1.29(TCK)_56") (pintype "bidirectional"))
    )
    (net (code "80") (name "unconnected-(U401-P1.30(TMS)-Pad52)") (class "Default")
      (node (ref "U401") (pin "52") (pinfunction "P1.30(TMS)_52") (pintype "bidirectional"))
    )
    (net (code "81") (name "unconnected-(U401-P1.31({slash}TRST)-Pad20)") (class "Default")
      (node (ref "U401") (pin "20") (pinfunction "P1.31(/TRST)_20") (pintype "bidirectional"))
    )
    (net (code "82") (name "unconnected-(U601-AUX_CL-Pad7)") (class "Default")
      (node (ref "U601") (pin "7") (pinfunction "AUX_CL_7") (pintype "bidirectional"))
    )
    (net (code "83") (name "unconnected-(U601-AUX_DA-Pad6)") (class "Default")
      (node (ref "U601") (pin "6") (pinfunction "AUX_DA_6") (pintype "bidirectional"))
    )
    (net (code "84") (name "unconnected-(U601-CLKOUT-Pad22)") (class "Default")
      (node (ref "U601") (pin "22") (pinfunction "CLKOUT_22") (pintype "bidirectional"))
    )
    (net (code "85") (name "unconnected-(U801-NC-Pad3)") (class "Default")
      (node (ref "U801") (pin "3") (pinfunction "NC_3") (pintype "bidirectional"))
    )
    (net (code "86") (name "unconnected-(U801-NC-Pad5)") (class "Default")
      (node (ref "U801") (pin "5") (pinfunction "NC_5") (pintype "bidirectional"))
    )
    (net (code "87") (name "unconnected-(U801-NC-Pad6)") (class "Default")
      (node (ref "U801") (pin "6") (pinfunction "NC_6") (pintype "bidirectional"))
    )
    (net (code "88") (name "unconnected-(U801-NC-Pad7)") (class "Default")
      (node (ref "U801") (pin "7") (pinfunction "NC_7") (pintype "bidirectional"))
    )
    (net (code "89") (name "unconnected-(U801-NC-Pad14)") (class "Default")
      (node (ref "U801") (pin "14") (pinfunction "NC_14") (pintype "bidirectional"))
    )
    (net (code "90") (name "unconnected-(U902-VIN2-Pad5)") (class "Default")
      (node (ref "U902") (pin "5") (pinfunction "VIN2_5") (pintype "bidirectional"))
    )
  )
)
